# BOTS_Latch.net
KiCad netlist of a schematic drawn in EAGLE
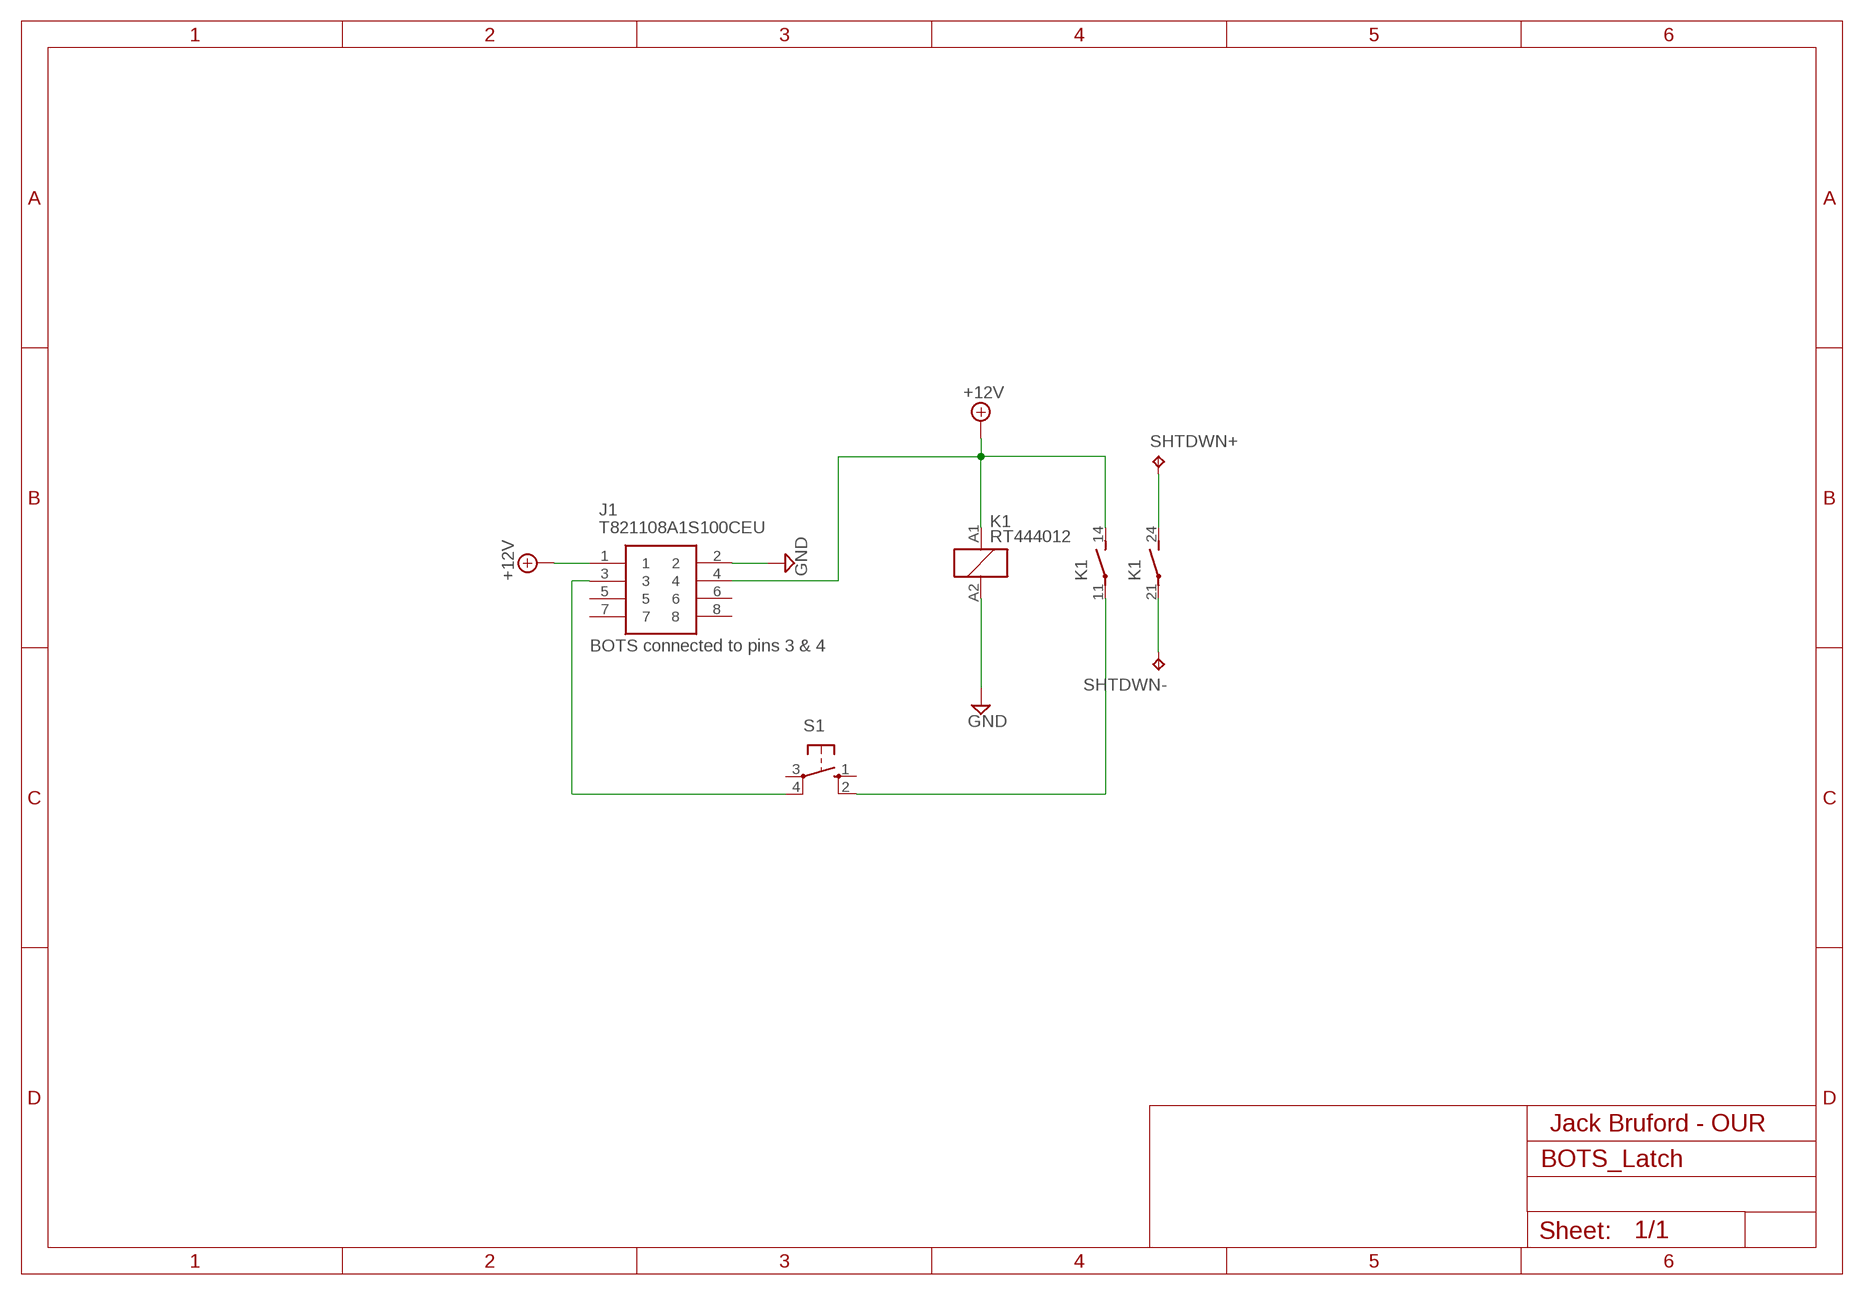
[diagram p0: schematic, sheet 1]

(export (version "E")
  (design (tool "Eeschema 10.0.6"))
  (components
    (comp (ref "J1")
      (value "T821108A1S100CEU")
      (footprint "eagle-import:HDRV8W64P254_2X4_1778X895X915P")
      (fields (field (name "RS_PART_NUMBER") "1702738"))
      (libsource (lib "eagle-import") (part "T821108A1S100CEU"))
    )
    (comp (ref "K1")
      (value "RT444012")
      (footprint "eagle-import:RT2N_O")
      (libsource (lib "eagle-import") (part "RT44?4012"))
    )
    (comp (ref "S1")
      (value "10-XX")
      (footprint "eagle-import:B3F-10XX")
      (fields (field (name "MPN") "B3F-1000"))
      (libsource (lib "eagle-import") (part "10-XX"))
    )
    (comp (ref "SHTDWN+")
      (value "TPPAD1-13")
      (footprint "eagle-import:P1-13")
      (libsource (lib "eagle-import") (part "TPPAD1-13"))
    )
    (comp (ref "SHTDWN-")
      (value "TPPAD1-13")
      (footprint "eagle-import:P1-13")
      (libsource (lib "eagle-import") (part "TPPAD1-13"))
    )
  )
  (nets
    (net (code "1") (name "+12V") (class "Default")
      (node (ref "J1") (pin "1") (pinfunction "1_1") (pintype "bidirectional"))
      (node (ref "J1") (pin "4") (pinfunction "4_4") (pintype "bidirectional"))
      (node (ref "K1") (pin "14") (pinfunction "S_14") (pintype "passive"))
      (node (ref "K1") (pin "A1") (pinfunction "1_A1") (pintype "passive"))
    )
    (net (code "2") (name "GND") (class "Default")
      (node (ref "J1") (pin "2") (pinfunction "2_2") (pintype "bidirectional"))
      (node (ref "K1") (pin "A2") (pinfunction "2_A2") (pintype "passive"))
    )
    (net (code "3") (name "Net-(K1B-P)") (class "Default")
      (node (ref "K1") (pin "11") (pinfunction "P_11") (pintype "passive"))
      (node (ref "S1") (pin "2") (pinfunction "S1_2") (pintype "passive"))
    )
    (net (code "4") (name "Net-(K1C-P)") (class "Default")
      (node (ref "K1") (pin "21") (pinfunction "P_21") (pintype "passive"))
      (node (ref "SHTDWN-") (pin "TP") (pinfunction "TP_TP") (pintype "input"))
    )
    (net (code "5") (name "Net-(K1C-S)") (class "Default")
      (node (ref "K1") (pin "24") (pinfunction "S_24") (pintype "passive"))
      (node (ref "SHTDWN+") (pin "TP") (pinfunction "TP_TP") (pintype "input"))
    )
    (net (code "6") (name "Net-(S1-P1)") (class "Default")
      (node (ref "J1") (pin "3") (pinfunction "3_3") (pintype "bidirectional"))
      (node (ref "S1") (pin "4") (pinfunction "P1_4") (pintype "passive"))
    )
    (net (code "7") (name "unconnected-(J1-Pad5)") (class "Default")
      (node (ref "J1") (pin "5") (pinfunction "5_5") (pintype "bidirectional"))
    )
    (net (code "8") (name "unconnected-(J1-Pad6)") (class "Default")
      (node (ref "J1") (pin "6") (pinfunction "6_6") (pintype "bidirectional"))
    )
    (net (code "9") (name "unconnected-(J1-Pad7)") (class "Default")
      (node (ref "J1") (pin "7") (pinfunction "7_7") (pintype "bidirectional"))
    )
    (net (code "10") (name "unconnected-(J1-Pad8)") (class "Default")
      (node (ref "J1") (pin "8") (pinfunction "8_8") (pintype "bidirectional"))
    )
    (net (code "11") (name "unconnected-(S1-P-Pad3)") (class "Default")
      (node (ref "S1") (pin "3") (pinfunction "P_3") (pintype "passive"))
    )
    (net (code "12") (name "unconnected-(S1-S-Pad1)") (class "Default")
      (node (ref "S1") (pin "1") (pinfunction "S_1") (pintype "passive"))
    )
  )
)
